# Encoder_iC-PX_v1b.net
KiCad netlist of a schematic drawn in EAGLE
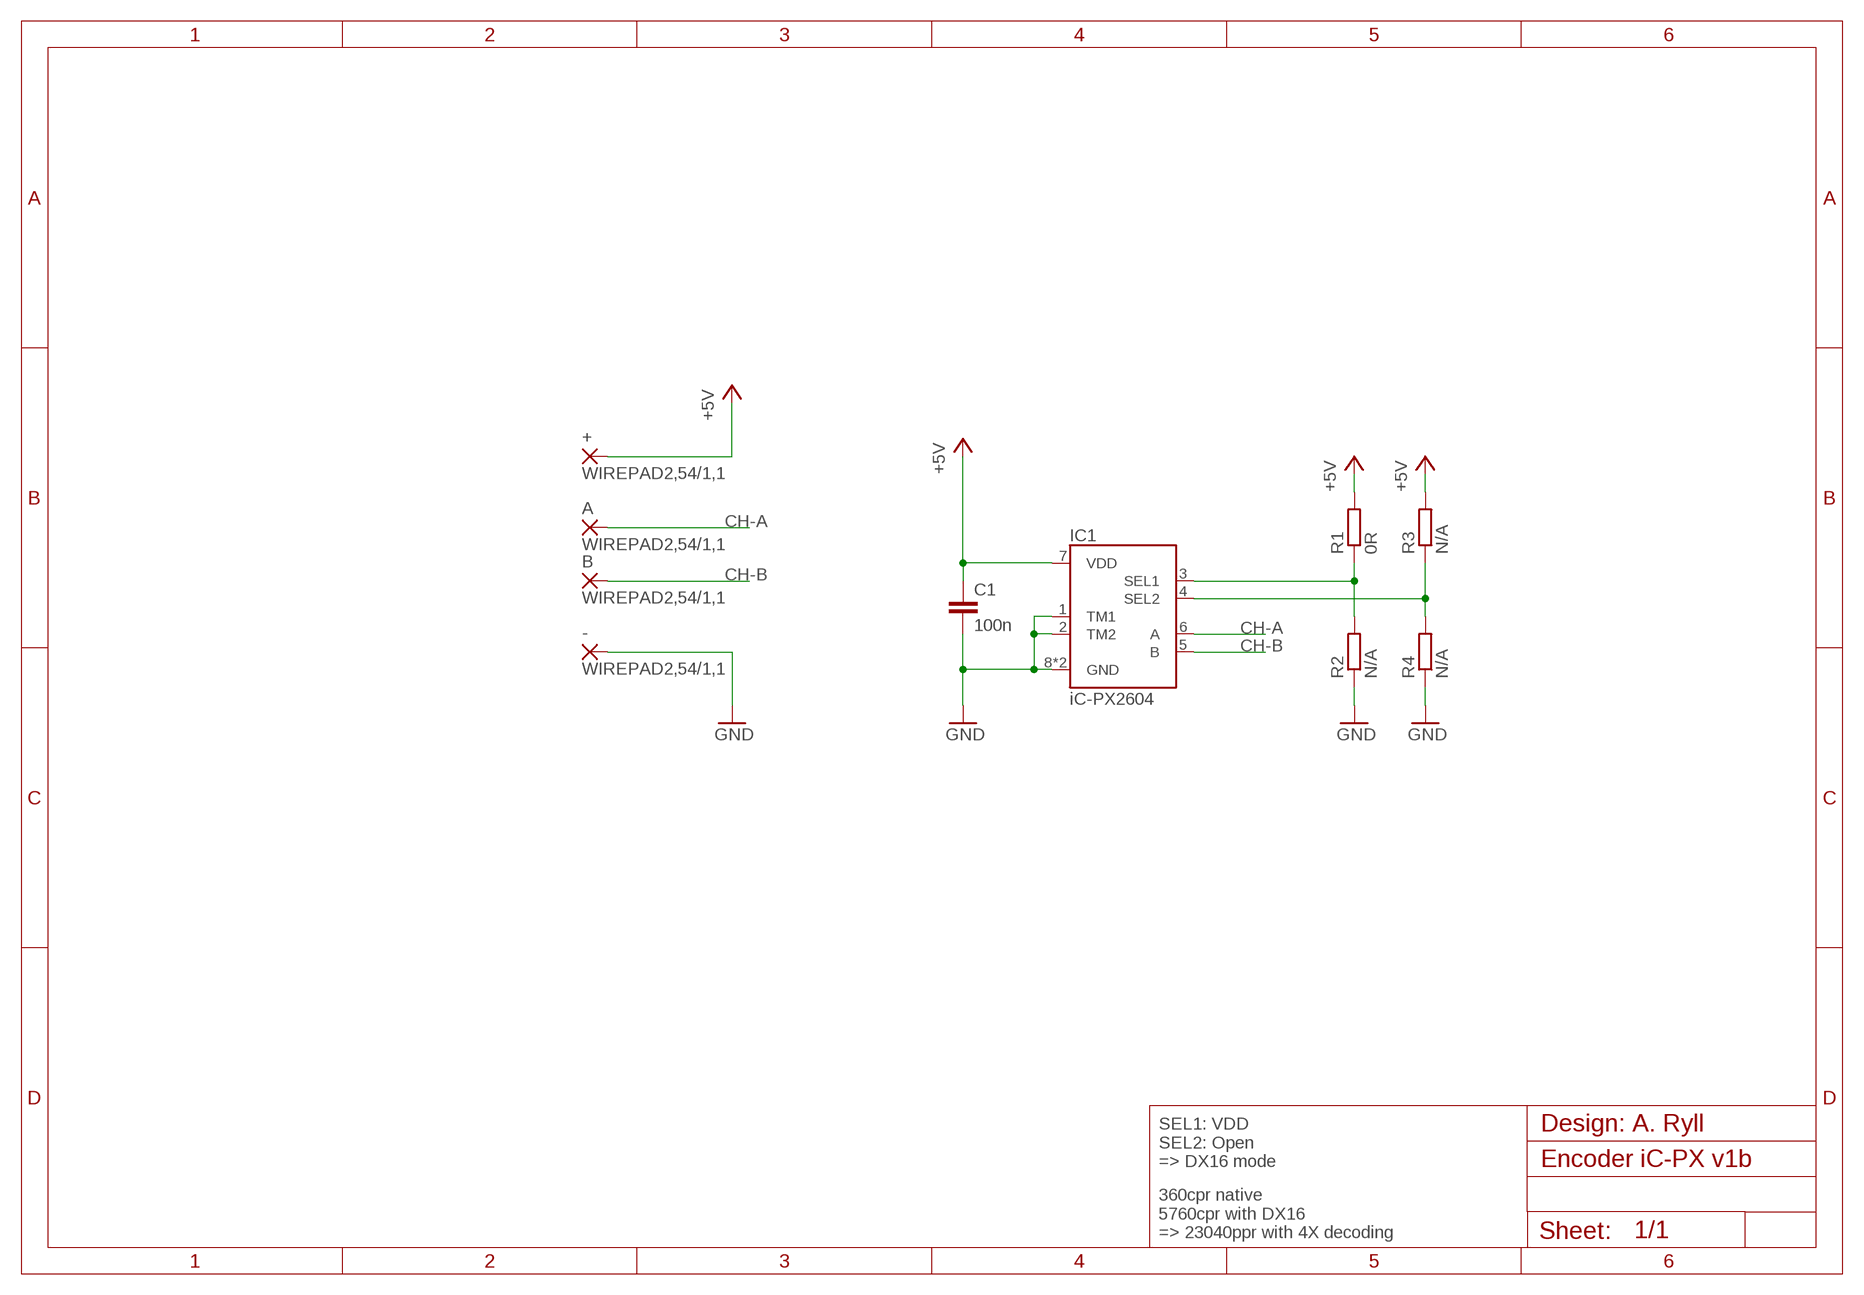
[diagram p0: schematic, sheet 1]

(export (version "E")
  (design (tool "Eeschema 10.0.6"))
  (components
    (comp (ref "+")
      (value "WIREPAD2,54/1,1")
      (footprint "eagle-import:2,54_1,1")
      (libsource (lib "eagle-import") (part "WIREPAD2,54/1,1"))
    )
    (comp (ref "-")
      (value "WIREPAD2,54/1,1")
      (footprint "eagle-import:2,54_1,1")
      (libsource (lib "eagle-import") (part "WIREPAD2,54/1,1"))
    )
    (comp (ref "A")
      (value "WIREPAD2,54/1,1")
      (footprint "eagle-import:2,54_1,1")
      (libsource (lib "eagle-import") (part "WIREPAD2,54/1,1"))
    )
    (comp (ref "B")
      (value "WIREPAD2,54/1,1")
      (footprint "eagle-import:2,54_1,1")
      (libsource (lib "eagle-import") (part "WIREPAD2,54/1,1"))
    )
    (comp (ref "C1")
      (value "100n")
      (footprint "eagle-import:C0603")
      (libsource (lib "eagle-import") (part "C-EUC0603"))
    )
    (comp (ref "IC1")
      (value "iC-PX2604")
      (footprint "eagle-import:ODFN8-3X3")
      (libsource (lib "eagle-import") (part "IC-PX"))
    )
    (comp (ref "R1")
      (value "0R")
      (footprint "eagle-import:R0603")
      (libsource (lib "eagle-import") (part "R-EU_R0603"))
    )
    (comp (ref "R2")
      (value "N/A")
      (footprint "eagle-import:R0603")
      (libsource (lib "eagle-import") (part "R-EU_R0603"))
    )
    (comp (ref "R3")
      (value "N/A")
      (footprint "eagle-import:R0603")
      (libsource (lib "eagle-import") (part "R-EU_R0603"))
    )
    (comp (ref "R4")
      (value "N/A")
      (footprint "eagle-import:R0603")
      (libsource (lib "eagle-import") (part "R-EU_R0603"))
    )
  )
  (nets
    (net (code "1") (name "+5V") (class "Default")
      (node (ref "+") (pin "1") (pinfunction "P_1") (pintype "passive"))
      (node (ref "C1") (pin "1") (pinfunction "1_1") (pintype "passive"))
      (node (ref "IC1") (pin "7") (pinfunction "VDD_7") (pintype "bidirectional"))
      (node (ref "R1") (pin "2") (pinfunction "2_2") (pintype "passive"))
      (node (ref "R3") (pin "2") (pinfunction "2_2") (pintype "passive"))
    )
    (net (code "2") (name "/CH-A") (class "Default")
      (node (ref "A") (pin "1") (pinfunction "P_1") (pintype "passive"))
      (node (ref "IC1") (pin "6") (pinfunction "A_6") (pintype "bidirectional"))
    )
    (net (code "3") (name "/CH-B") (class "Default")
      (node (ref "B") (pin "1") (pinfunction "P_1") (pintype "passive"))
      (node (ref "IC1") (pin "5") (pinfunction "B_5") (pintype "bidirectional"))
    )
    (net (code "4") (name "GND") (class "Default")
      (node (ref "-") (pin "1") (pinfunction "P_1") (pintype "passive"))
      (node (ref "C1") (pin "2") (pinfunction "2_2") (pintype "passive"))
      (node (ref "IC1") (pin "1") (pinfunction "TM1_1") (pintype "bidirectional"))
      (node (ref "IC1") (pin "2") (pinfunction "TM2_2") (pintype "bidirectional"))
      (node (ref "IC1") (pin "8") (pinfunction "GND_8") (pintype "bidirectional"))
      (node (ref "IC1") (pin "BP") (pinfunction "GND_BP") (pintype "bidirectional"))
      (node (ref "R2") (pin "1") (pinfunction "1_1") (pintype "passive"))
      (node (ref "R4") (pin "1") (pinfunction "1_1") (pintype "passive"))
    )
    (net (code "5") (name "Net-(IC1-SEL1)") (class "Default")
      (node (ref "IC1") (pin "3") (pinfunction "SEL1_3") (pintype "bidirectional"))
      (node (ref "R1") (pin "1") (pinfunction "1_1") (pintype "passive"))
      (node (ref "R2") (pin "2") (pinfunction "2_2") (pintype "passive"))
    )
    (net (code "6") (name "Net-(IC1-SEL2)") (class "Default")
      (node (ref "IC1") (pin "4") (pinfunction "SEL2_4") (pintype "bidirectional"))
      (node (ref "R3") (pin "1") (pinfunction "1_1") (pintype "passive"))
      (node (ref "R4") (pin "2") (pinfunction "2_2") (pintype "passive"))
    )
  )
)
